# POWER.net
KiCad netlist of a schematic drawn in Altium Designer
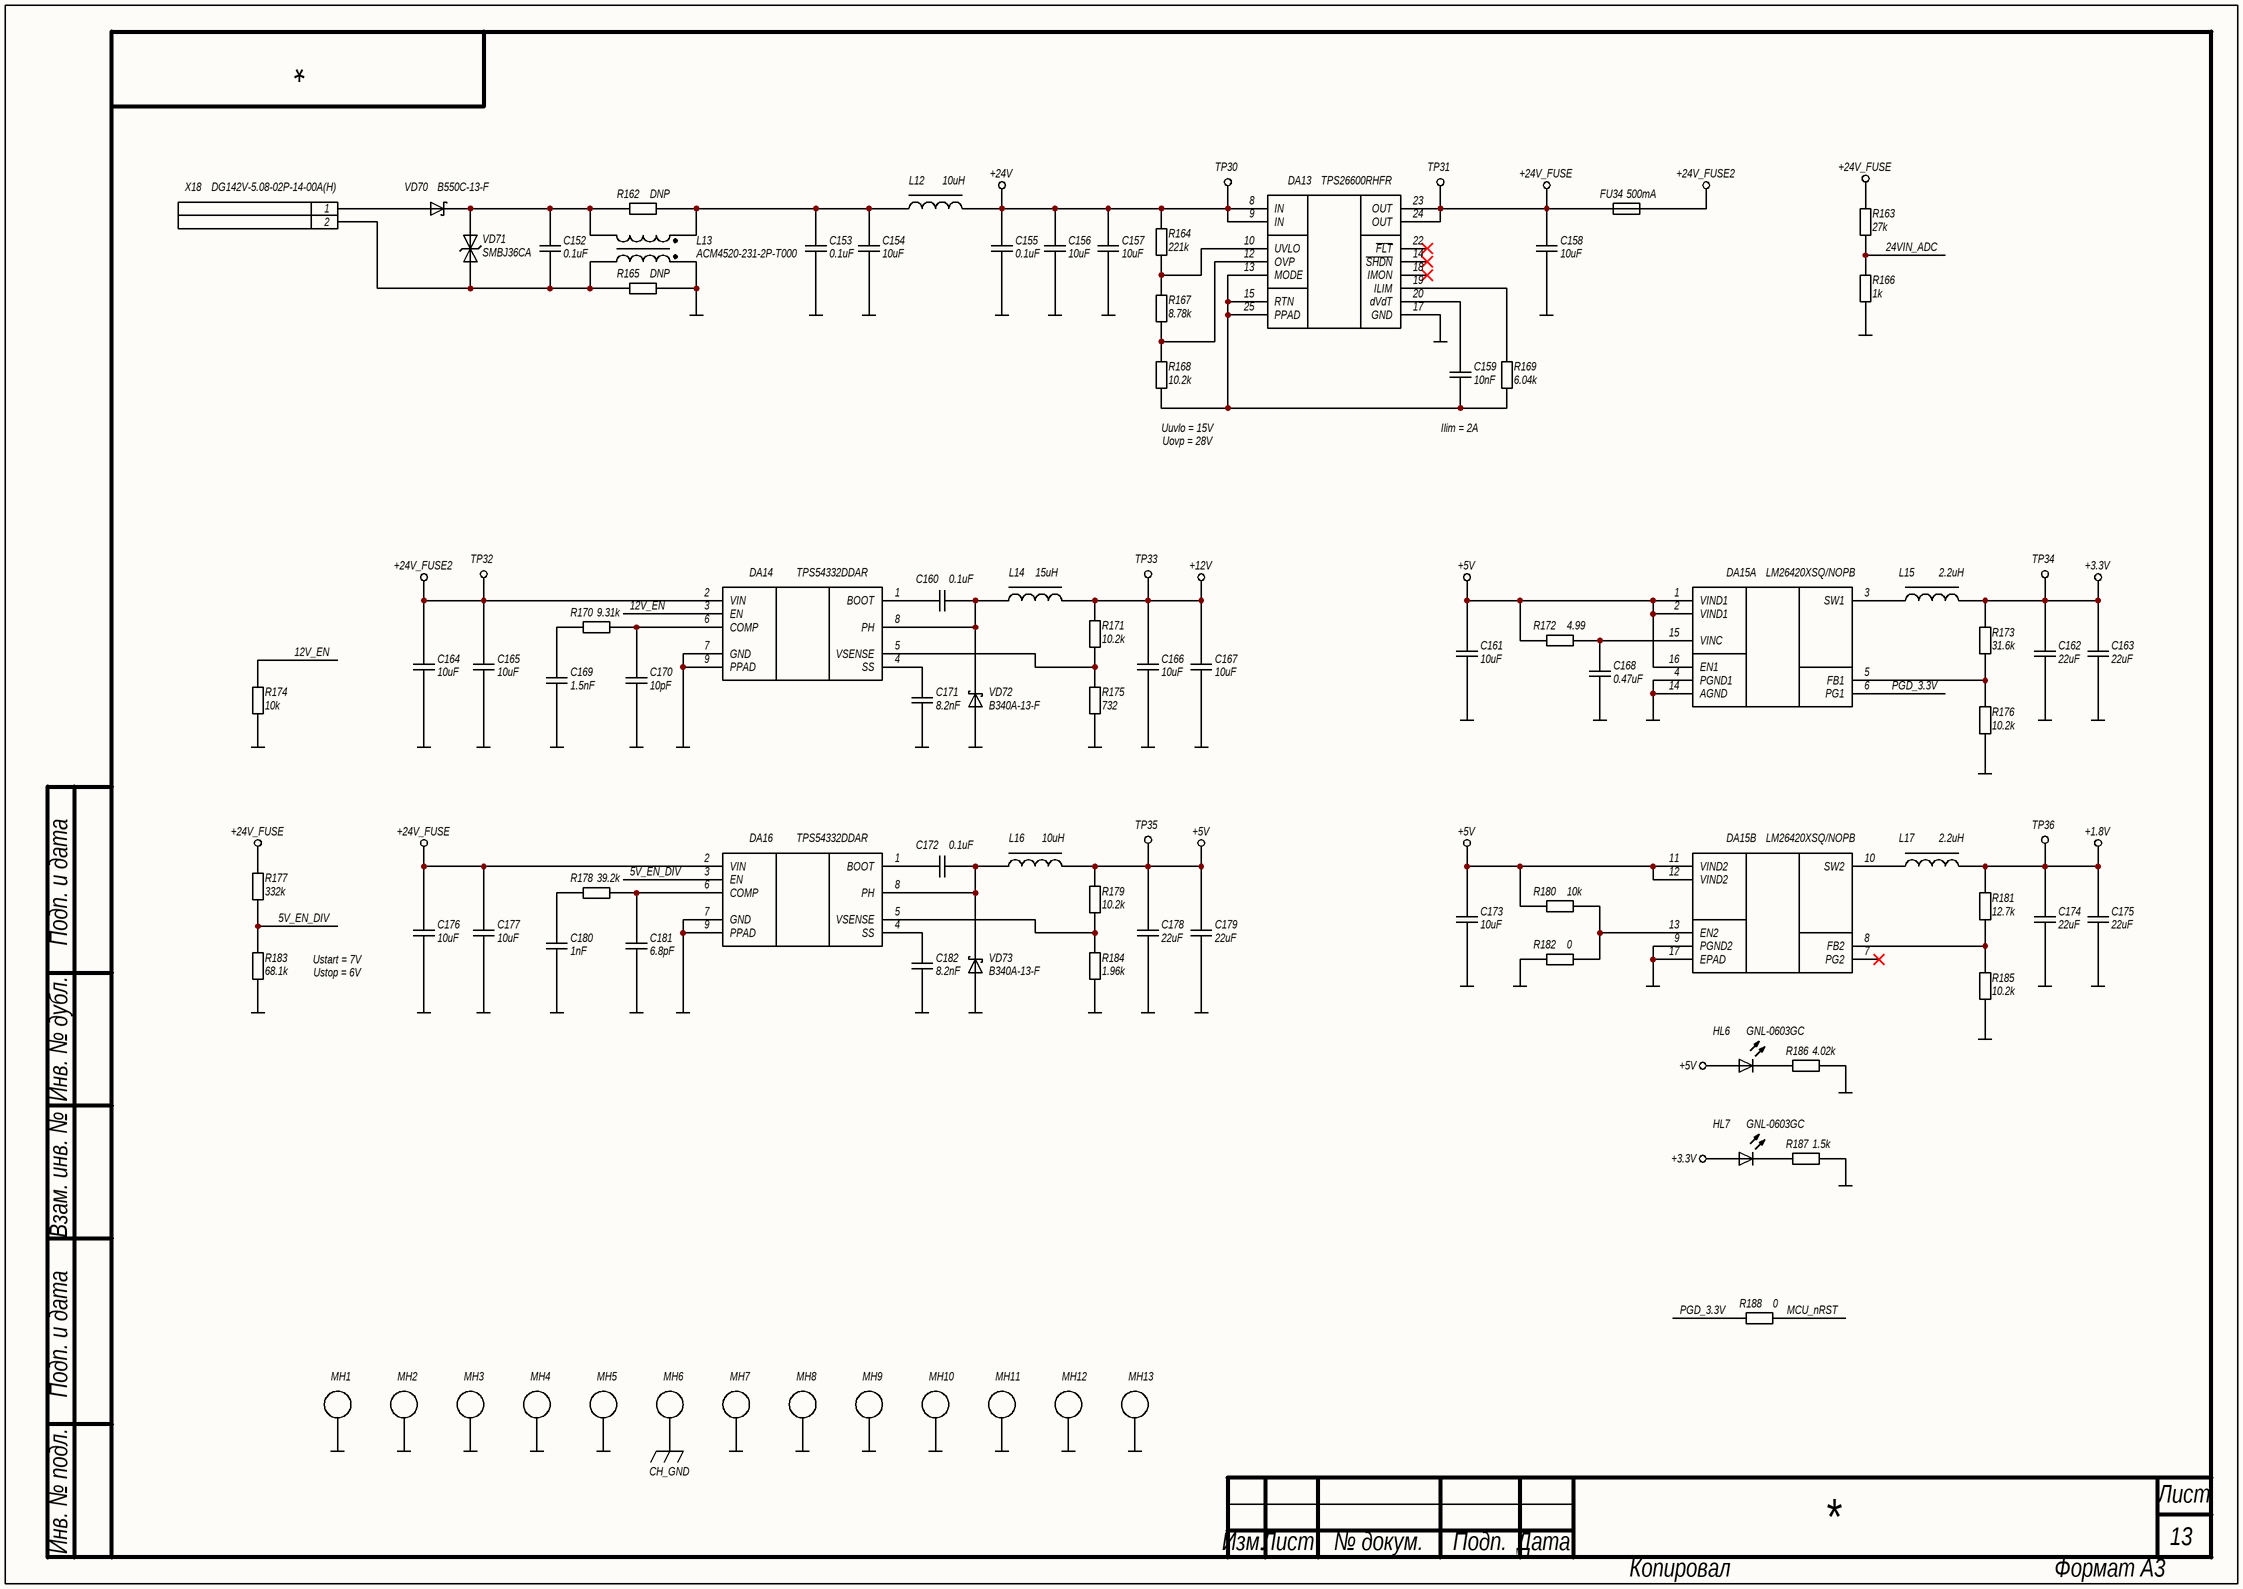
[diagram p0: POWER.SchDoc]

(export (version "E")
  (design (tool "Eeschema 10.0.6"))
  (components
    (comp (ref "C152")
      (value "0.1uF")
      (footprint "C0805N")
      (description "Конденсатор")
      (libsource (lib "Components Library") (part "CAP_FIXED"))
    )
    (comp (ref "C153")
      (value "0.1uF")
      (footprint "C0805N")
      (description "Конденсатор")
      (libsource (lib "Components Library") (part "CAP_FIXED"))
    )
    (comp (ref "C154")
      (value "10uF")
      (footprint "C1206N")
      (description "Конденсатор")
      (libsource (lib "Components Library") (part "CAP_FIXED"))
    )
    (comp (ref "C155")
      (value "0.1uF")
      (footprint "C0805N")
      (description "Конденсатор")
      (libsource (lib "Components Library") (part "CAP_FIXED"))
    )
    (comp (ref "C156")
      (value "10uF")
      (footprint "C1206N")
      (description "Конденсатор")
      (libsource (lib "Components Library") (part "CAP_FIXED"))
    )
    (comp (ref "C157")
      (value "10uF")
      (footprint "C1206N")
      (description "Конденсатор")
      (libsource (lib "Components Library") (part "CAP_FIXED"))
    )
    (comp (ref "C158")
      (value "10uF")
      (footprint "C1206N")
      (description "Конденсатор")
      (libsource (lib "Components Library") (part "CAP_FIXED"))
    )
    (comp (ref "C159")
      (value "10nF")
      (footprint "C0603N")
      (description "Конденсатор")
      (libsource (lib "Components Library") (part "CAP_FIXED"))
    )
    (comp (ref "C160")
      (value "0.1uF")
      (footprint "C0603N")
      (description "Конденсатор")
      (libsource (lib "Components Library") (part "CAP_FIXED"))
    )
    (comp (ref "C161")
      (value "10uF")
      (footprint "C0805N")
      (description "Конденсатор")
      (libsource (lib "Components Library") (part "CAP_FIXED"))
    )
    (comp (ref "C162")
      (value "22uF")
      (footprint "C0805N")
      (description "Конденсатор")
      (libsource (lib "Components Library") (part "CAP_FIXED"))
    )
    (comp (ref "C163")
      (value "22uF")
      (footprint "C0805N")
      (description "Конденсатор")
      (libsource (lib "Components Library") (part "CAP_FIXED"))
    )
    (comp (ref "C164")
      (value "10uF")
      (footprint "C1206N")
      (description "Конденсатор")
      (libsource (lib "Components Library") (part "CAP_FIXED"))
    )
    (comp (ref "C165")
      (value "10uF")
      (footprint "C1206N")
      (description "Конденсатор")
      (libsource (lib "Components Library") (part "CAP_FIXED"))
    )
    (comp (ref "C166")
      (value "10uF")
      (footprint "C0805N")
      (description "Конденсатор")
      (libsource (lib "Components Library") (part "CAP_FIXED"))
    )
    (comp (ref "C167")
      (value "10uF")
      (footprint "C0805N")
      (description "Конденсатор")
      (libsource (lib "Components Library") (part "CAP_FIXED"))
    )
    (comp (ref "C168")
      (value "0.47uF")
      (footprint "C0603N")
      (description "Конденсатор")
      (libsource (lib "Components Library") (part "CAP_FIXED"))
    )
    (comp (ref "C169")
      (value "1.5nF")
      (footprint "C0603N")
      (description "Конденсатор")
      (libsource (lib "Components Library") (part "CAP_FIXED"))
    )
    (comp (ref "C170")
      (value "10pF")
      (footprint "C0603N")
      (description "Конденсатор")
      (libsource (lib "Components Library") (part "CAP_FIXED"))
    )
    (comp (ref "C171")
      (value "8.2nF")
      (footprint "C0603N")
      (description "Конденсатор")
      (libsource (lib "Components Library") (part "CAP_FIXED"))
    )
    (comp (ref "C172")
      (value "0.1uF")
      (footprint "C0603N")
      (description "Конденсатор")
      (libsource (lib "Components Library") (part "CAP_FIXED"))
    )
    (comp (ref "C173")
      (value "10uF")
      (footprint "C0805N")
      (description "Конденсатор")
      (libsource (lib "Components Library") (part "CAP_FIXED"))
    )
    (comp (ref "C174")
      (value "22uF")
      (footprint "C0805N")
      (description "Конденсатор")
      (libsource (lib "Components Library") (part "CAP_FIXED"))
    )
    (comp (ref "C175")
      (value "22uF")
      (footprint "C0805N")
      (description "Конденсатор")
      (libsource (lib "Components Library") (part "CAP_FIXED"))
    )
    (comp (ref "C176")
      (value "10uF")
      (footprint "C1206N")
      (description "Конденсатор")
      (libsource (lib "Components Library") (part "CAP_FIXED"))
    )
    (comp (ref "C177")
      (value "10uF")
      (footprint "C1206N")
      (description "Конденсатор")
      (libsource (lib "Components Library") (part "CAP_FIXED"))
    )
    (comp (ref "C178")
      (value "22uF")
      (footprint "C0805N")
      (description "Конденсатор")
      (libsource (lib "Components Library") (part "CAP_FIXED"))
    )
    (comp (ref "C179")
      (value "22uF")
      (footprint "C0805N")
      (description "Конденсатор")
      (libsource (lib "Components Library") (part "CAP_FIXED"))
    )
    (comp (ref "C180")
      (value "1nF")
      (footprint "C0603N")
      (description "Конденсатор")
      (libsource (lib "Components Library") (part "CAP_FIXED"))
    )
    (comp (ref "C181")
      (value "6.8pF")
      (footprint "C0603N")
      (description "Конденсатор")
      (libsource (lib "Components Library") (part "CAP_FIXED"))
    )
    (comp (ref "C182")
      (value "8.2nF")
      (footprint "C0603N")
      (description "Конденсатор")
      (libsource (lib "Components Library") (part "CAP_FIXED"))
    )
    (comp (ref "DA13")
      (value "TPS26600RHFR")
      (footprint "RHF0024A (VQFN-24 EP)")
      (description "Микросхема eFuse")
      (libsource (lib "Components Library") (part "TPS2660xRHF"))
    )
    (comp (ref "DA14")
      (value "TPS54332DDAR")
      (footprint "SOIC8-EP")
      (description "Микросхема понижающего преобразователя")
      (libsource (lib "Components Library") (part "TPS54332"))
    )
    (comp (ref "DA15")
      (value "LM26420XSQ/NOPB")
      (footprint "RUM0016A")
      (libsource (lib "Components Library") (part "LM26420X"))
    )
    (comp (ref "DA16")
      (value "TPS54332DDAR")
      (footprint "SOIC8-EP")
      (description "Микросхема понижающего преобразователя")
      (libsource (lib "Components Library") (part "TPS54332"))
    )
    (comp (ref "FU34")
      (value "500mA")
      (footprint "MF-MSMF")
      (description "Плавкий предохранитель")
      (libsource (lib "Components Library") (part "FUSE"))
    )
    (comp (ref "HL6")
      (value "GNL-0603GC")
      (footprint "LED0603")
      (description "Светодиод")
      (libsource (lib "Components Library") (part "LED"))
    )
    (comp (ref "HL7")
      (value "GNL-0603GC")
      (footprint "LED0603")
      (description "Светодиод")
      (libsource (lib "Components Library") (part "LED"))
    )
    (comp (ref "L12")
      (value "10uH")
      (footprint "SRN8040")
      (description "Дроссель с магнитопроводом")
      (libsource (lib "Components Library") (part "IND_CORE"))
    )
    (comp (ref "L13")
      (value "ACM4520-231-2P-T000")
      (footprint "ACM4520")
      (description "Синфазный дроссель")
      (libsource (lib "Components Library") (part "IND_CMC"))
    )
    (comp (ref "L14")
      (value "15uH")
      (footprint "SRN8040")
      (description "Дроссель с магнитопроводом")
      (libsource (lib "Components Library") (part "IND_CORE"))
    )
    (comp (ref "L15")
      (value "2.2uH")
      (footprint "VLS3012HBX")
      (description "Дроссель с магнитопроводом")
      (libsource (lib "Components Library") (part "IND_CORE"))
    )
    (comp (ref "L16")
      (value "10uH")
      (footprint "SRN8040")
      (description "Дроссель с магнитопроводом")
      (libsource (lib "Components Library") (part "IND_CORE"))
    )
    (comp (ref "L17")
      (value "2.2uH")
      (footprint "VLS3012HBX")
      (description "Дроссель с магнитопроводом")
      (libsource (lib "Components Library") (part "IND_CORE"))
    )
    (comp (ref "MH1")
      (value "MNT_HOLE_PL")
      (footprint "MH_3.2_5.4_PLATED_VIA")
      (description "Монтажное отверстие, металлизированное")
      (libsource (lib "Components Library") (part "MNT_HOLE_PL"))
    )
    (comp (ref "MH2")
      (value "MNT_HOLE_PL")
      (footprint "MH_3.2_5.4_PLATED_VIA")
      (description "Монтажное отверстие, металлизированное")
      (libsource (lib "Components Library") (part "MNT_HOLE_PL"))
    )
    (comp (ref "MH3")
      (value "MNT_HOLE_PL")
      (footprint "MH_3.2_5.4_PLATED_VIA")
      (description "Монтажное отверстие, металлизированное")
      (libsource (lib "Components Library") (part "MNT_HOLE_PL"))
    )
    (comp (ref "MH4")
      (value "MNT_HOLE_PL")
      (footprint "MH_3.2_5.4_PLATED_VIA")
      (description "Монтажное отверстие, металлизированное")
      (libsource (lib "Components Library") (part "MNT_HOLE_PL"))
    )
    (comp (ref "MH5")
      (value "MNT_HOLE_PL")
      (footprint "MH_3.2_5.4_PLATED_VIA")
      (description "Монтажное отверстие, металлизированное")
      (libsource (lib "Components Library") (part "MNT_HOLE_PL"))
    )
    (comp (ref "MH6")
      (value "MNT_HOLE_PL")
      (footprint "MH_3.2_5.4_PLATED_VIA")
      (description "Монтажное отверстие, металлизированное")
      (libsource (lib "Components Library") (part "MNT_HOLE_PL"))
    )
    (comp (ref "MH7")
      (value "MNT_HOLE_PL")
      (footprint "MH_3.2_5.4_PLATED_VIA")
      (description "Монтажное отверстие, металлизированное")
      (libsource (lib "Components Library") (part "MNT_HOLE_PL"))
    )
    (comp (ref "MH8")
      (value "MNT_HOLE_PL")
      (footprint "MH_3.2_5.4_PLATED_VIA")
      (description "Монтажное отверстие, металлизированное")
      (libsource (lib "Components Library") (part "MNT_HOLE_PL"))
    )
    (comp (ref "MH9")
      (value "MNT_HOLE_PL")
      (footprint "MH_3.2_5.4_PLATED_VIA")
      (description "Монтажное отверстие, металлизированное")
      (libsource (lib "Components Library") (part "MNT_HOLE_PL"))
    )
    (comp (ref "MH10")
      (value "MNT_HOLE_PL")
      (footprint "MH_3.2_5.4_PLATED_VIA")
      (description "Монтажное отверстие, металлизированное")
      (libsource (lib "Components Library") (part "MNT_HOLE_PL"))
    )
    (comp (ref "MH11")
      (value "MNT_HOLE_PL")
      (footprint "MH_3.2_5.4_PLATED_VIA")
      (description "Монтажное отверстие, металлизированное")
      (libsource (lib "Components Library") (part "MNT_HOLE_PL"))
    )
    (comp (ref "MH12")
      (value "MNT_HOLE_PL")
      (footprint "MH_3.2_5.4_PLATED_VIA")
      (description "Монтажное отверстие, металлизированное")
      (libsource (lib "Components Library") (part "MNT_HOLE_PL"))
    )
    (comp (ref "MH13")
      (value "MNT_HOLE_PL")
      (footprint "MH_3.2_5.4_PLATED_VIA")
      (description "Монтажное отверстие, металлизированное")
      (libsource (lib "Components Library") (part "MNT_HOLE_PL"))
    )
    (comp (ref "R162")
      (value "DNP")
      (footprint "R1206N")
      (description "Резистор")
      (libsource (lib "") (part "RES_FIXED_3"))
    )
    (comp (ref "R163")
      (value "27k")
      (footprint "R0603N")
      (description "Резистор")
      (libsource (lib "Components Library") (part "RES_FIXED"))
    )
    (comp (ref "R164")
      (value "221k")
      (footprint "R0603N")
      (description "Резистор")
      (libsource (lib "Components Library") (part "RES_FIXED"))
    )
    (comp (ref "R165")
      (value "DNP")
      (footprint "R1206N")
      (description "Резистор")
      (libsource (lib "") (part "RES_FIXED_3"))
    )
    (comp (ref "R166")
      (value "1k")
      (footprint "R0603N")
      (description "Резистор")
      (libsource (lib "Components Library") (part "RES_FIXED"))
    )
    (comp (ref "R167")
      (value "8.78k")
      (footprint "R0603N")
      (description "Резистор")
      (libsource (lib "Components Library") (part "RES_FIXED"))
    )
    (comp (ref "R168")
      (value "10.2k")
      (footprint "R0603N")
      (description "Резистор")
      (libsource (lib "") (part "RES_FIXED_2"))
    )
    (comp (ref "R169")
      (value "6.04k")
      (footprint "R0603N")
      (description "Резистор")
      (libsource (lib "Components Library") (part "RES_FIXED"))
    )
    (comp (ref "R170")
      (value "9.31k")
      (footprint "R0603N")
      (description "Резистор")
      (libsource (lib "") (part "RES_FIXED_1"))
    )
    (comp (ref "R171")
      (value "10.2k")
      (footprint "R0603N")
      (description "Резистор")
      (libsource (lib "") (part "RES_FIXED_2"))
    )
    (comp (ref "R172")
      (value "4.99")
      (footprint "R0603N")
      (description "Резистор")
      (libsource (lib "") (part "RES_FIXED_1"))
    )
    (comp (ref "R173")
      (value "31.6k")
      (footprint "R0603N")
      (description "Резистор")
      (libsource (lib "") (part "RES_FIXED_2"))
    )
    (comp (ref "R174")
      (value "10k")
      (footprint "R0603N")
      (description "Резистор")
      (libsource (lib "Components Library") (part "RES_FIXED"))
    )
    (comp (ref "R175")
      (value "732")
      (footprint "R0603N")
      (description "Резистор")
      (libsource (lib "") (part "RES_FIXED_2"))
    )
    (comp (ref "R176")
      (value "10.2k")
      (footprint "R0603N")
      (description "Резистор")
      (libsource (lib "") (part "RES_FIXED_2"))
    )
    (comp (ref "R177")
      (value "332k")
      (footprint "R0603N")
      (description "Резистор")
      (libsource (lib "") (part "RES_FIXED_2"))
    )
    (comp (ref "R178")
      (value "39.2k")
      (footprint "R0603N")
      (description "Резистор")
      (libsource (lib "") (part "RES_FIXED_1"))
    )
    (comp (ref "R179")
      (value "10.2k")
      (footprint "R0603N")
      (description "Резистор")
      (libsource (lib "") (part "RES_FIXED_2"))
    )
    (comp (ref "R180")
      (value "10k")
      (footprint "R0603N")
      (description "Резистор")
      (libsource (lib "") (part "RES_FIXED_1"))
    )
    (comp (ref "R181")
      (value "12.7k")
      (footprint "R0603N")
      (description "Резистор")
      (libsource (lib "") (part "RES_FIXED_2"))
    )
    (comp (ref "R182")
      (value "0")
      (footprint "R0603N")
      (description "Резистор")
      (libsource (lib "") (part "RES_FIXED_1"))
    )
    (comp (ref "R183")
      (value "68.1k")
      (footprint "R0603N")
      (description "Резистор")
      (libsource (lib "") (part "RES_FIXED_2"))
    )
    (comp (ref "R184")
      (value "1.96k")
      (footprint "R0603N")
      (description "Резистор")
      (libsource (lib "") (part "RES_FIXED_2"))
    )
    (comp (ref "R185")
      (value "10.2k")
      (footprint "R0603N")
      (description "Резистор")
      (libsource (lib "") (part "RES_FIXED_2"))
    )
    (comp (ref "R186")
      (value "4.02k")
      (footprint "R0603N")
      (description "Резистор")
      (libsource (lib "") (part "RES_FIXED_1"))
    )
    (comp (ref "R187")
      (value "1.5k")
      (footprint "R0603N")
      (description "Резистор")
      (libsource (lib "") (part "RES_FIXED_1"))
    )
    (comp (ref "R188")
      (value "0")
      (footprint "R0603N")
      (description "Резистор")
      (libsource (lib "") (part "RES_FIXED_3"))
    )
    (comp (ref "TP30")
      (value "TEST_POINT")
      (footprint "TP_RPAD_0.8MM")
      (description "Контрольная точка")
      (libsource (lib "Components Library") (part "TEST_POINT"))
    )
    (comp (ref "TP31")
      (value "TEST_POINT")
      (footprint "TP_RPAD_0.8MM")
      (description "Контрольная точка")
      (libsource (lib "Components Library") (part "TEST_POINT"))
    )
    (comp (ref "TP32")
      (value "TEST_POINT")
      (footprint "TP_RPAD_0.8MM")
      (description "Контрольная точка")
      (libsource (lib "Components Library") (part "TEST_POINT"))
    )
    (comp (ref "TP33")
      (value "TEST_POINT")
      (footprint "TP_RPAD_0.8MM")
      (description "Контрольная точка")
      (libsource (lib "Components Library") (part "TEST_POINT"))
    )
    (comp (ref "TP34")
      (value "TEST_POINT")
      (footprint "TP_RPAD_0.8MM")
      (description "Контрольная точка")
      (libsource (lib "Components Library") (part "TEST_POINT"))
    )
    (comp (ref "TP35")
      (value "TEST_POINT")
      (footprint "TP_RPAD_0.8MM")
      (description "Контрольная точка")
      (libsource (lib "Components Library") (part "TEST_POINT"))
    )
    (comp (ref "TP36")
      (value "TEST_POINT")
      (footprint "TP_RPAD_0.8MM")
      (description "Контрольная точка")
      (libsource (lib "Components Library") (part "TEST_POINT"))
    )
    (comp (ref "VD70")
      (value "B550C-13-F")
      (footprint "SMC")
      (description "Диод Шоттки")
      (libsource (lib "Components Library") (part "SCHOTTKY"))
    )
    (comp (ref "VD71")
      (value "SMBJ36CA")
      (footprint "SMB")
      (description "TVS диод двунаправленный")
      (libsource (lib "Components Library") (part "TVS_BIDIR"))
    )
    (comp (ref "VD72")
      (value "B340A-13-F")
      (footprint "SMA")
      (description "Диод Шоттки")
      (libsource (lib "Components Library") (part "SCHOTTKY"))
    )
    (comp (ref "VD73")
      (value "B340A-13-F")
      (footprint "SMA")
      (description "Диод Шоттки")
      (libsource (lib "Components Library") (part "SCHOTTKY"))
    )
    (comp (ref "X18")
      (value "DG142V-5.08-02P-14-00A(H)")
      (footprint "DG142V-5.08-02P-14-00A(H)")
      (description "Разъем, 2 контакта")
      (libsource (lib "Components Library") (part "Connector 2"))
    )
  )
  (nets
    (net (code "1") (name "+1.8V") (class "Default")
      (node (ref "C174") (pin "2") (pinfunction "2_2") (pintype "passive"))
      (node (ref "C175") (pin "2") (pinfunction "2_2") (pintype "passive"))
      (node (ref "L17") (pin "2") (pinfunction "2_2") (pintype "passive"))
      (node (ref "R181") (pin "1") (pinfunction "1_1") (pintype "passive"))
      (node (ref "TP36") (pin "1") (pinfunction "1_1") (pintype "passive"))
    )
    (net (code "2") (name "+3.3V") (class "Default")
      (node (ref "C162") (pin "2") (pinfunction "2_2") (pintype "passive"))
      (node (ref "C163") (pin "2") (pinfunction "2_2") (pintype "passive"))
      (node (ref "HL7") (pin "2") (pinfunction "A_2") (pintype "passive"))
      (node (ref "L15") (pin "2") (pinfunction "2_2") (pintype "passive"))
      (node (ref "R173") (pin "1") (pinfunction "1_1") (pintype "passive"))
      (node (ref "TP34") (pin "1") (pinfunction "1_1") (pintype "passive"))
    )
    (net (code "3") (name "+5V") (class "Default")
      (node (ref "C161") (pin "2") (pinfunction "2_2") (pintype "passive"))
      (node (ref "C173") (pin "2") (pinfunction "2_2") (pintype "passive"))
      (node (ref "C178") (pin "2") (pinfunction "2_2") (pintype "passive"))
      (node (ref "C179") (pin "2") (pinfunction "2_2") (pintype "passive"))
      (node (ref "DA15") (pin "1") (pinfunction "VIND1_1") (pintype "power_in"))
      (node (ref "DA15") (pin "11") (pinfunction "VIND2_11") (pintype "power_in"))
      (node (ref "DA15") (pin "12") (pinfunction "VIND2_12") (pintype "power_in"))
      (node (ref "DA15") (pin "16") (pinfunction "EN1_16") (pintype "power_in"))
      (node (ref "DA15") (pin "2") (pinfunction "VIND1_2") (pintype "power_in"))
      (node (ref "HL6") (pin "2") (pinfunction "A_2") (pintype "passive"))
      (node (ref "L16") (pin "2") (pinfunction "2_2") (pintype "passive"))
      (node (ref "R172") (pin "2") (pinfunction "2_2") (pintype "passive"))
      (node (ref "R179") (pin "1") (pinfunction "1_1") (pintype "passive"))
      (node (ref "R180") (pin "2") (pinfunction "2_2") (pintype "passive"))
      (node (ref "TP35") (pin "1") (pinfunction "1_1") (pintype "passive"))
    )
    (net (code "4") (name "+12V") (class "Default")
      (node (ref "C166") (pin "2") (pinfunction "2_2") (pintype "passive"))
      (node (ref "C167") (pin "2") (pinfunction "2_2") (pintype "passive"))
      (node (ref "L14") (pin "2") (pinfunction "2_2") (pintype "passive"))
      (node (ref "R171") (pin "1") (pinfunction "1_1") (pintype "passive"))
      (node (ref "TP33") (pin "1") (pinfunction "1_1") (pintype "passive"))
    )
    (net (code "5") (name "+24V") (class "Default")
      (node (ref "C155") (pin "2") (pinfunction "2_2") (pintype "passive"))
      (node (ref "C156") (pin "2") (pinfunction "2_2") (pintype "passive"))
      (node (ref "C157") (pin "2") (pinfunction "2_2") (pintype "passive"))
      (node (ref "DA13") (pin "8") (pinfunction "IN_8") (pintype "power_in"))
      (node (ref "DA13") (pin "9") (pinfunction "IN_9") (pintype "power_in"))
      (node (ref "L12") (pin "2") (pinfunction "2_2") (pintype "passive"))
      (node (ref "R164") (pin "2") (pinfunction "2_2") (pintype "passive"))
      (node (ref "TP30") (pin "1") (pinfunction "1_1") (pintype "passive"))
    )
    (net (code "6") (name "+24V_FUSE") (class "Default")
      (node (ref "C158") (pin "2") (pinfunction "2_2") (pintype "passive"))
      (node (ref "C176") (pin "2") (pinfunction "2_2") (pintype "passive"))
      (node (ref "C177") (pin "2") (pinfunction "2_2") (pintype "passive"))
      (node (ref "DA13") (pin "23") (pinfunction "OUT_23") (pintype "power_in"))
      (node (ref "DA13") (pin "24") (pinfunction "OUT_24") (pintype "power_in"))
      (node (ref "DA16") (pin "2") (pinfunction "VIN_2") (pintype "power_in"))
      (node (ref "FU34") (pin "1") (pinfunction "1_1") (pintype "passive"))
      (node (ref "R163") (pin "2") (pinfunction "2_2") (pintype "passive"))
      (node (ref "R177") (pin "1") (pinfunction "1_1") (pintype "passive"))
      (node (ref "TP31") (pin "1") (pinfunction "1_1") (pintype "passive"))
    )
    (net (code "7") (name "+24V_FUSE2") (class "Default")
      (node (ref "C164") (pin "2") (pinfunction "2_2") (pintype "passive"))
      (node (ref "C165") (pin "2") (pinfunction "2_2") (pintype "passive"))
      (node (ref "DA14") (pin "2") (pinfunction "VIN_2") (pintype "power_in"))
      (node (ref "FU34") (pin "2") (pinfunction "2_2") (pintype "passive"))
      (node (ref "TP32") (pin "1") (pinfunction "1_1") (pintype "passive"))
    )
    (net (code "8") (name "/5V_EN_DIV") (class "Default")
      (node (ref "DA16") (pin "3") (pinfunction "EN_3") (pintype "power_in"))
      (node (ref "R177") (pin "2") (pinfunction "2_2") (pintype "passive"))
      (node (ref "R183") (pin "1") (pinfunction "1_1") (pintype "passive"))
    )
    (net (code "9") (name "/12V_EN") (class "Default")
      (node (ref "DA14") (pin "3") (pinfunction "EN_3") (pintype "power_in"))
      (node (ref "R174") (pin "2") (pinfunction "2_2") (pintype "passive"))
    )
    (net (code "10") (name "/24VIN_ADC") (class "Default")
      (node (ref "R163") (pin "1") (pinfunction "1_1") (pintype "passive"))
      (node (ref "R166") (pin "2") (pinfunction "2_2") (pintype "passive"))
    )
    (net (code "11") (name "/MCU_nRST") (class "Default")
      (node (ref "R188") (pin "2") (pinfunction "2_2") (pintype "passive"))
    )
    (net (code "12") (name "/PGD_3.3V") (class "Default")
      (node (ref "DA15") (pin "6") (pinfunction "PG1_6") (pintype "power_in"))
      (node (ref "R188") (pin "1") (pinfunction "1_1") (pintype "passive"))
    )
    (net (code "13") (name "CH_GND") (class "Default")
      (node (ref "MH6") (pin "1") (pinfunction "1_1") (pintype "passive"))
    )
    (net (code "14") (name "GND") (class "Default")
      (node (ref "C153") (pin "1") (pinfunction "1_1") (pintype "passive"))
      (node (ref "C154") (pin "1") (pinfunction "1_1") (pintype "passive"))
      (node (ref "C155") (pin "1") (pinfunction "1_1") (pintype "passive"))
      (node (ref "C156") (pin "1") (pinfunction "1_1") (pintype "passive"))
      (node (ref "C157") (pin "1") (pinfunction "1_1") (pintype "passive"))
      (node (ref "C158") (pin "1") (pinfunction "1_1") (pintype "passive"))
      (node (ref "C161") (pin "1") (pinfunction "1_1") (pintype "passive"))
      (node (ref "C162") (pin "1") (pinfunction "1_1") (pintype "passive"))
      (node (ref "C163") (pin "1") (pinfunction "1_1") (pintype "passive"))
      (node (ref "C164") (pin "1") (pinfunction "1_1") (pintype "passive"))
      (node (ref "C165") (pin "1") (pinfunction "1_1") (pintype "passive"))
      (node (ref "C166") (pin "1") (pinfunction "1_1") (pintype "passive"))
      (node (ref "C167") (pin "1") (pinfunction "1_1") (pintype "passive"))
      (node (ref "C168") (pin "1") (pinfunction "1_1") (pintype "passive"))
      (node (ref "C169") (pin "1") (pinfunction "1_1") (pintype "passive"))
      (node (ref "C170") (pin "1") (pinfunction "1_1") (pintype "passive"))
      (node (ref "C171") (pin "1") (pinfunction "1_1") (pintype "passive"))
      (node (ref "C173") (pin "1") (pinfunction "1_1") (pintype "passive"))
      (node (ref "C174") (pin "1") (pinfunction "1_1") (pintype "passive"))
      (node (ref "C175") (pin "1") (pinfunction "1_1") (pintype "passive"))
      (node (ref "C176") (pin "1") (pinfunction "1_1") (pintype "passive"))
      (node (ref "C177") (pin "1") (pinfunction "1_1") (pintype "passive"))
      (node (ref "C178") (pin "1") (pinfunction "1_1") (pintype "passive"))
      (node (ref "C179") (pin "1") (pinfunction "1_1") (pintype "passive"))
      (node (ref "C180") (pin "1") (pinfunction "1_1") (pintype "passive"))
      (node (ref "C181") (pin "1") (pinfunction "1_1") (pintype "passive"))
      (node (ref "C182") (pin "1") (pinfunction "1_1") (pintype "passive"))
      (node (ref "DA13") (pin "17") (pinfunction "GND_17") (pintype "power_in"))
      (node (ref "DA14") (pin "7") (pinfunction "GND_7") (pintype "power_in"))
      (node (ref "DA14") (pin "9") (pinfunction "PPAD_9") (pintype "power_in"))
      (node (ref "DA15") (pin "14") (pinfunction "AGND_14") (pintype "power_in"))
      (node (ref "DA15") (pin "17") (pinfunction "EPAD_17") (pintype "power_in"))
      (node (ref "DA15") (pin "4") (pinfunction "PGND1_4") (pintype "power_in"))
      (node (ref "DA15") (pin "9") (pinfunction "PGND2_9") (pintype "power_in"))
      (node (ref "DA16") (pin "7") (pinfunction "GND_7") (pintype "power_in"))
      (node (ref "DA16") (pin "9") (pinfunction "PPAD_9") (pintype "power_in"))
      (node (ref "L13") (pin "1") (pinfunction "1_1") (pintype "passive"))
      (node (ref "MH1") (pin "1") (pinfunction "1_1") (pintype "passive"))
      (node (ref "MH10") (pin "1") (pinfunction "1_1") (pintype "passive"))
      (node (ref "MH11") (pin "1") (pinfunction "1_1") (pintype "passive"))
      (node (ref "MH12") (pin "1") (pinfunction "1_1") (pintype "passive"))
      (node (ref "MH13") (pin "1") (pinfunction "1_1") (pintype "passive"))
      (node (ref "MH2") (pin "1") (pinfunction "1_1") (pintype "passive"))
      (node (ref "MH3") (pin "1") (pinfunction "1_1") (pintype "passive"))
      (node (ref "MH4") (pin "1") (pinfunction "1_1") (pintype "passive"))
      (node (ref "MH5") (pin "1") (pinfunction "1_1") (pintype "passive"))
      (node (ref "MH7") (pin "1") (pinfunction "1_1") (pintype "passive"))
      (node (ref "MH8") (pin "1") (pinfunction "1_1") (pintype "passive"))
      (node (ref "MH9") (pin "1") (pinfunction "1_1") (pintype "passive"))
      (node (ref "R165") (pin "2") (pinfunction "2_2") (pintype "passive"))
      (node (ref "R166") (pin "1") (pinfunction "1_1") (pintype "passive"))
      (node (ref "R174") (pin "1") (pinfunction "1_1") (pintype "passive"))
      (node (ref "R175") (pin "2") (pinfunction "2_2") (pintype "passive"))
      (node (ref "R176") (pin "2") (pinfunction "2_2") (pintype "passive"))
      (node (ref "R182") (pin "2") (pinfunction "2_2") (pintype "passive"))
      (node (ref "R183") (pin "2") (pinfunction "2_2") (pintype "passive"))
      (node (ref "R184") (pin "2") (pinfunction "2_2") (pintype "passive"))
      (node (ref "R185") (pin "2") (pinfunction "2_2") (pintype "passive"))
      (node (ref "R186") (pin "1") (pinfunction "1_1") (pintype "passive"))
      (node (ref "R187") (pin "1") (pinfunction "1_1") (pintype "passive"))
      (node (ref "VD72") (pin "2") (pinfunction "A_2") (pintype "passive"))
      (node (ref "VD73") (pin "2") (pinfunction "A_2") (pintype "passive"))
    )
    (net (code "15") (name "Net-(C153-Pad2)") (class "Default")
      (node (ref "C153") (pin "2") (pinfunction "2_2") (pintype "passive"))
      (node (ref "C154") (pin "2") (pinfunction "2_2") (pintype "passive"))
      (node (ref "L12") (pin "1") (pinfunction "1_1") (pintype "passive"))
      (node (ref "L13") (pin "4") (pinfunction "4_4") (pintype "passive"))
      (node (ref "R162") (pin "2") (pinfunction "2_2") (pintype "passive"))
    )
    (net (code "16") (name "Net-(C169-Pad2)") (class "Default")
      (node (ref "C169") (pin "2") (pinfunction "2_2") (pintype "passive"))
      (node (ref "R170") (pin "2") (pinfunction "2_2") (pintype "passive"))
    )
    (net (code "17") (name "Net-(C180-Pad2)") (class "Default")
      (node (ref "C180") (pin "2") (pinfunction "2_2") (pintype "passive"))
      (node (ref "R178") (pin "2") (pinfunction "2_2") (pintype "passive"))
    )
    (net (code "18") (name "Net-(DA13-ILIM)") (class "Default")
      (node (ref "DA13") (pin "19") (pinfunction "ILIM_19") (pintype "power_in"))
      (node (ref "R169") (pin "2") (pinfunction "2_2") (pintype "passive"))
    )
    (net (code "19") (name "Net-(DA13-MODE)") (class "Default")
      (node (ref "C159") (pin "2") (pinfunction "2_2") (pintype "passive"))
      (node (ref "DA13") (pin "13") (pinfunction "MODE_13") (pintype "power_in"))
      (node (ref "DA13") (pin "15") (pinfunction "RTN_15") (pintype "power_in"))
      (node (ref "DA13") (pin "25") (pinfunction "PPAD_25") (pintype "power_in"))
      (node (ref "R168") (pin "2") (pinfunction "2_2") (pintype "passive"))
      (node (ref "R169") (pin "1") (pinfunction "1_1") (pintype "passive"))
    )
    (net (code "20") (name "Net-(DA13-OVP)") (class "Default")
      (node (ref "DA13") (pin "12") (pinfunction "OVP_12") (pintype "power_in"))
      (node (ref "R167") (pin "1") (pinfunction "1_1") (pintype "passive"))
      (node (ref "R168") (pin "1") (pinfunction "1_1") (pintype "passive"))
    )
    (net (code "21") (name "Net-(DA13-UVLO)") (class "Default")
      (node (ref "DA13") (pin "10") (pinfunction "UVLO_10") (pintype "power_in"))
      (node (ref "R164") (pin "1") (pinfunction "1_1") (pintype "passive"))
      (node (ref "R167") (pin "2") (pinfunction "2_2") (pintype "passive"))
    )
    (net (code "22") (name "Net-(DA13-dVdT)") (class "Default")
      (node (ref "C159") (pin "1") (pinfunction "1_1") (pintype "passive"))
      (node (ref "DA13") (pin "20") (pinfunction "dVdT_20") (pintype "power_in"))
    )
    (net (code "23") (name "Net-(DA14-BOOT)") (class "Default")
      (node (ref "C160") (pin "2") (pinfunction "2_2") (pintype "passive"))
      (node (ref "DA14") (pin "1") (pinfunction "BOOT_1") (pintype "power_in"))
    )
    (net (code "24") (name "Net-(DA14-COMP)") (class "Default")
      (node (ref "C170") (pin "2") (pinfunction "2_2") (pintype "passive"))
      (node (ref "DA14") (pin "6") (pinfunction "COMP_6") (pintype "power_in"))
      (node (ref "R170") (pin "1") (pinfunction "1_1") (pintype "passive"))
    )
    (net (code "25") (name "Net-(DA14-PH)") (class "Default")
      (node (ref "C160") (pin "1") (pinfunction "1_1") (pintype "passive"))
      (node (ref "DA14") (pin "8") (pinfunction "PH_8") (pintype "power_in"))
      (node (ref "L14") (pin "1") (pinfunction "1_1") (pintype "passive"))
      (node (ref "VD72") (pin "1") (pinfunction "K_1") (pintype "passive"))
    )
    (net (code "26") (name "Net-(DA14-SS)") (class "Default")
      (node (ref "C171") (pin "2") (pinfunction "2_2") (pintype "passive"))
      (node (ref "DA14") (pin "4") (pinfunction "SS_4") (pintype "power_in"))
    )
    (net (code "27") (name "Net-(DA14-VSENSE)") (class "Default")
      (node (ref "DA14") (pin "5") (pinfunction "VSENSE_5") (pintype "power_in"))
      (node (ref "R171") (pin "2") (pinfunction "2_2") (pintype "passive"))
      (node (ref "R175") (pin "1") (pinfunction "1_1") (pintype "passive"))
    )
    (net (code "28") (name "Net-(DA15A-FB1)") (class "Default")
      (node (ref "DA15") (pin "5") (pinfunction "FB1_5") (pintype "power_in"))
      (node (ref "R173") (pin "2") (pinfunction "2_2") (pintype "passive"))
      (node (ref "R176") (pin "1") (pinfunction "1_1") (pintype "passive"))
    )
    (net (code "29") (name "Net-(DA15A-SW1)") (class "Default")
      (node (ref "DA15") (pin "3") (pinfunction "SW1_3") (pintype "power_in"))
      (node (ref "L15") (pin "1") (pinfunction "1_1") (pintype "passive"))
    )
    (net (code "30") (name "Net-(DA15A-VINC)") (class "Default")
      (node (ref "C168") (pin "2") (pinfunction "2_2") (pintype "passive"))
      (node (ref "DA15") (pin "15") (pinfunction "VINC_15") (pintype "power_in"))
      (node (ref "R172") (pin "1") (pinfunction "1_1") (pintype "passive"))
    )
    (net (code "31") (name "Net-(DA15B-EN2)") (class "Default")
      (node (ref "DA15") (pin "13") (pinfunction "EN2_13") (pintype "power_in"))
      (node (ref "R180") (pin "1") (pinfunction "1_1") (pintype "passive"))
      (node (ref "R182") (pin "1") (pinfunction "1_1") (pintype "passive"))
    )
    (net (code "32") (name "Net-(DA15B-FB2)") (class "Default")
      (node (ref "DA15") (pin "8") (pinfunction "FB2_8") (pintype "power_in"))
      (node (ref "R181") (pin "2") (pinfunction "2_2") (pintype "passive"))
      (node (ref "R185") (pin "1") (pinfunction "1_1") (pintype "passive"))
    )
    (net (code "33") (name "Net-(DA15B-SW2)") (class "Default")
      (node (ref "DA15") (pin "10") (pinfunction "SW2_10") (pintype "power_in"))
      (node (ref "L17") (pin "1") (pinfunction "1_1") (pintype "passive"))
    )
    (net (code "34") (name "Net-(DA16-BOOT)") (class "Default")
      (node (ref "C172") (pin "2") (pinfunction "2_2") (pintype "passive"))
      (node (ref "DA16") (pin "1") (pinfunction "BOOT_1") (pintype "power_in"))
    )
    (net (code "35") (name "Net-(DA16-COMP)") (class "Default")
      (node (ref "C181") (pin "2") (pinfunction "2_2") (pintype "passive"))
      (node (ref "DA16") (pin "6") (pinfunction "COMP_6") (pintype "power_in"))
      (node (ref "R178") (pin "1") (pinfunction "1_1") (pintype "passive"))
    )
    (net (code "36") (name "Net-(DA16-PH)") (class "Default")
      (node (ref "C172") (pin "1") (pinfunction "1_1") (pintype "passive"))
      (node (ref "DA16") (pin "8") (pinfunction "PH_8") (pintype "power_in"))
      (node (ref "L16") (pin "1") (pinfunction "1_1") (pintype "passive"))
      (node (ref "VD73") (pin "1") (pinfunction "K_1") (pintype "passive"))
    )
    (net (code "37") (name "Net-(DA16-SS)") (class "Default")
      (node (ref "C182") (pin "2") (pinfunction "2_2") (pintype "passive"))
      (node (ref "DA16") (pin "4") (pinfunction "SS_4") (pintype "power_in"))
    )
    (net (code "38") (name "Net-(DA16-VSENSE)") (class "Default")
      (node (ref "DA16") (pin "5") (pinfunction "VSENSE_5") (pintype "power_in"))
      (node (ref "R179") (pin "2") (pinfunction "2_2") (pintype "passive"))
      (node (ref "R184") (pin "1") (pinfunction "1_1") (pintype "passive"))
    )
    (net (code "39") (name "Net-(HL6-K)") (class "Default")
      (node (ref "HL6") (pin "1") (pinfunction "K_1") (pintype "passive"))
      (node (ref "R186") (pin "2") (pinfunction "2_2") (pintype "passive"))
    )
    (net (code "40") (name "Net-(HL7-K)") (class "Default")
      (node (ref "HL7") (pin "1") (pinfunction "K_1") (pintype "passive"))
      (node (ref "R187") (pin "2") (pinfunction "2_2") (pintype "passive"))
    )
    (net (code "41") (name "Net-(VD70-A)") (class "Default")
      (node (ref "VD70") (pin "2") (pinfunction "A_2") (pintype "passive"))
      (node (ref "X18") (pin "1") (pinfunction "1_1") (pintype "power_in"))
    )
    (net (code "42") (name "Net-(VD70-K)") (class "Default")
      (node (ref "C152") (pin "2") (pinfunction "2_2") (pintype "passive"))
      (node (ref "L13") (pin "3") (pinfunction "3_3") (pintype "passive"))
      (node (ref "R162") (pin "1") (pinfunction "1_1") (pintype "passive"))
      (node (ref "VD70") (pin "1") (pinfunction "K_1") (pintype "passive"))
      (node (ref "VD71") (pin "1") (pinfunction "A1_1") (pintype "passive"))
    )
    (net (code "43") (name "Net-(VD71-A2)") (class "Default")
      (node (ref "C152") (pin "1") (pinfunction "1_1") (pintype "passive"))
      (node (ref "L13") (pin "2") (pinfunction "2_2") (pintype "passive"))
      (node (ref "R165") (pin "1") (pinfunction "1_1") (pintype "passive"))
      (node (ref "VD71") (pin "2") (pinfunction "A2_2") (pintype "passive"))
      (node (ref "X18") (pin "2") (pinfunction "2_2") (pintype "power_in"))
    )
    (net (code "44") (name "unconnected-(DA13-IMON-Pad18)") (class "Default")
      (node (ref "DA13") (pin "18") (pinfunction "IMON_18") (pintype "power_in+no_connect"))
    )
    (net (code "45") (name "unconnected-(DA13-~{FLT}-Pad22)") (class "Default")
      (node (ref "DA13") (pin "22") (pinfunction "~{FLT}_22") (pintype "power_in+no_connect"))
    )
    (net (code "46") (name "unconnected-(DA13-~{SHDN}-Pad14)") (class "Default")
      (node (ref "DA13") (pin "14") (pinfunction "~{SHDN}_14") (pintype "power_in+no_connect"))
    )
    (net (code "47") (name "unconnected-(DA15B-PG2-Pad7)") (class "Default")
      (node (ref "DA15") (pin "7") (pinfunction "PG2_7") (pintype "power_in+no_connect"))
    )
  )
)
